# Sheet1.net
KiCad netlist of a schematic drawn in Altium Designer
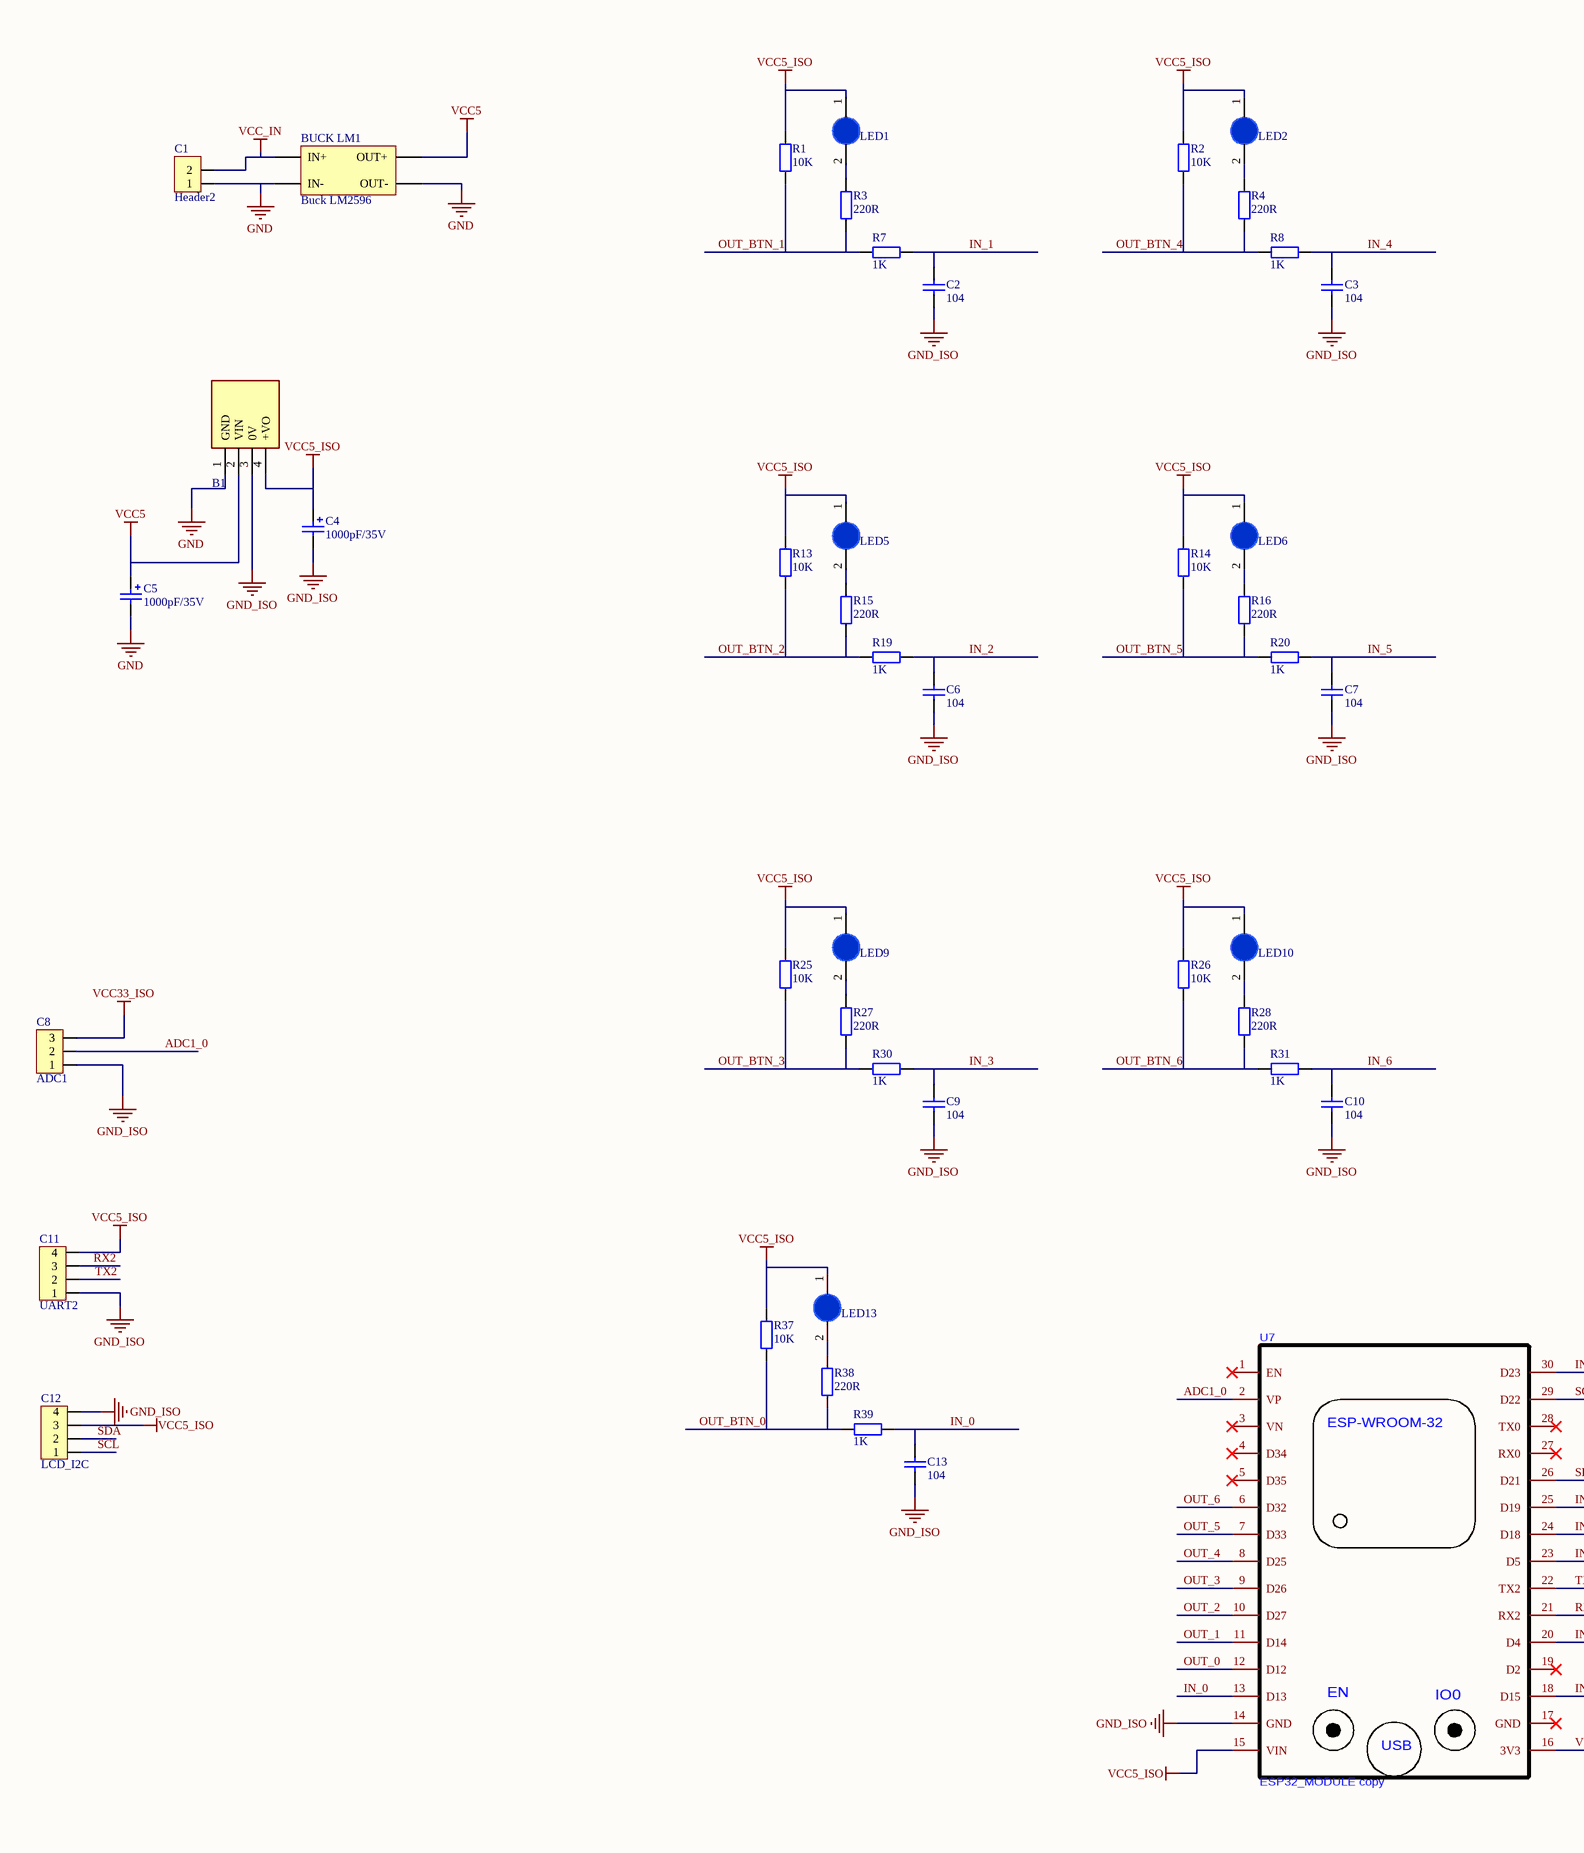
[diagram p0: Sheet1.SchDoc, left]
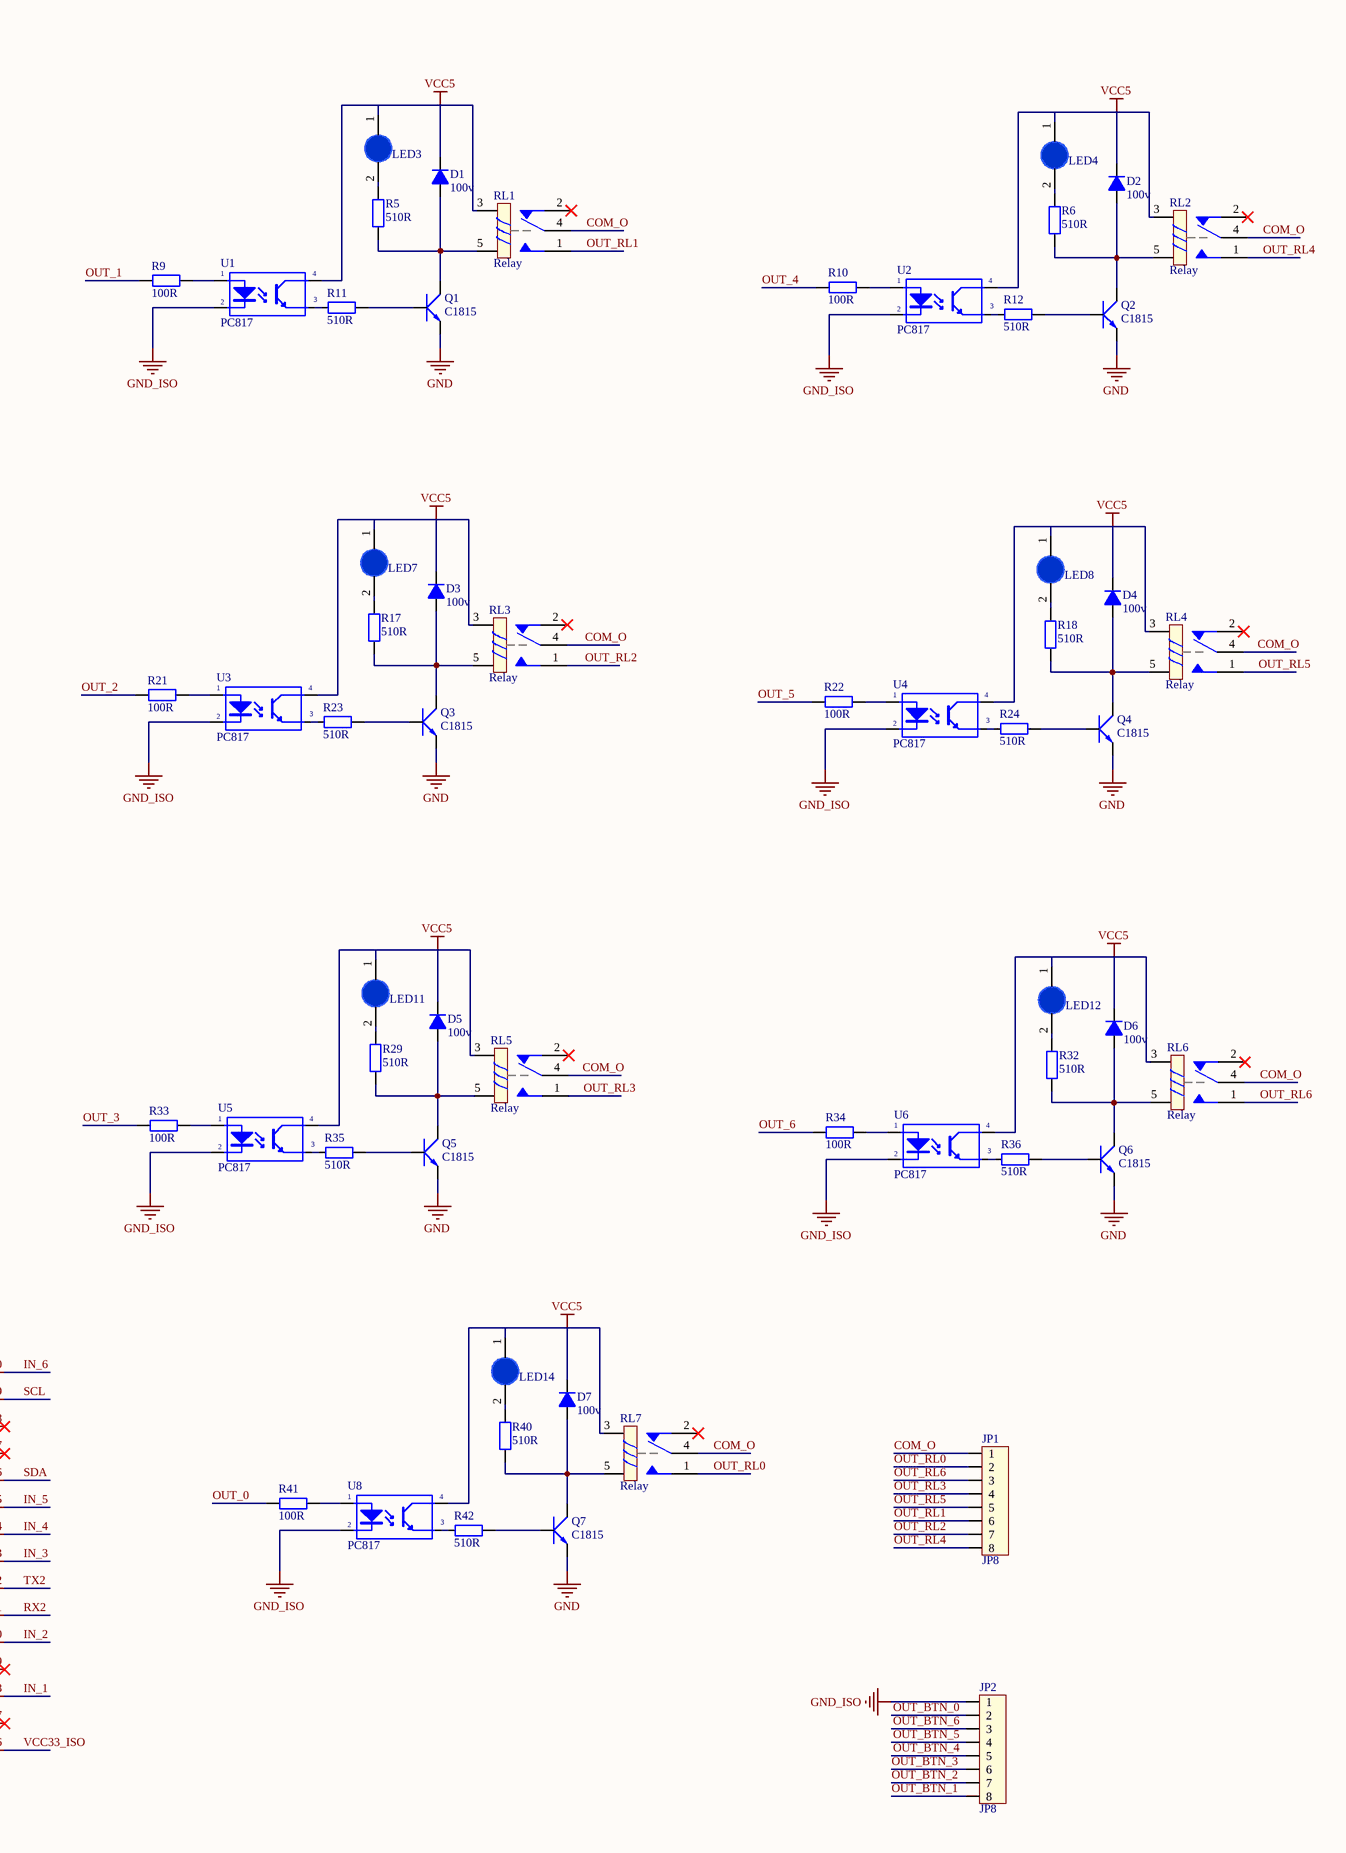
[diagram p1: Sheet1.SchDoc, right]

(export (version "E")
  (design (tool "Eeschema 10.0.6"))
  (components
    (comp (ref "B1")
      (value "B0505S1W")
      (footprint "B0505S1W")
      (description "Power Supply")
      (fields (field (name "MANUFACTURER_PART_NUMBER") "B0505S-1W"))
      (libsource (lib "myLib_v1") (part "B0505S1W"))
    )
    (comp (ref "BUCK LM1")
      (value "Buck LM2596")
      (footprint "BUCK LM2596")
      (libsource (lib "myLib_v1") (part "Buck LM2596"))
    )
    (comp (ref "C1")
      (value "Header2")
      (footprint "Header2")
      (description "Header IDC, 2 x 1 Pin Vertical 2.54mm Pitch (Non-Boxed, Male)")
      (fields
        (field (name "MANUFACTURER") "Würth Elektronik eiSos GmbH")
        (field (name "PARTNO") "613002143121")
        (field (name "CREATED BY") "Karrer Zheng")
      )
      (libsource (lib "myLib_v1") (part "Header2"))
    )
    (comp (ref "C2")
      (value "104")
      (footprint "tu gom")
      (description "Cắm")
      (libsource (lib "Altium_Lib_by_KhueNguyenCreator") (part "Tu gom 104 50V"))
    )
    (comp (ref "C3")
      (value "104")
      (footprint "tu gom")
      (description "Cắm")
      (libsource (lib "Altium_Lib_by_KhueNguyenCreator") (part "Tu gom 104 50V"))
    )
    (comp (ref "C4")
      (value "1000pF/35V")
      (footprint "CP2/5")
      (description "Polarized Capacitor (Surface Mount)")
      (fields (field (name "Comment") "Cap Pol3") (field (name "PUBLISHER") "Altium Limited"))
      (libsource (lib "myLib_v1") (part "Cap Pol3"))
    )
    (comp (ref "C5")
      (value "1000pF/35V")
      (footprint "CP2/5")
      (description "Polarized Capacitor (Surface Mount)")
      (fields (field (name "Comment") "Cap Pol3") (field (name "PUBLISHER") "Altium Limited"))
      (libsource (lib "myLib_v1") (part "Cap Pol3"))
    )
    (comp (ref "C6")
      (value "104")
      (footprint "tu gom")
      (description "Cắm")
      (libsource (lib "Altium_Lib_by_KhueNguyenCreator") (part "Tu gom 104 50V"))
    )
    (comp (ref "C7")
      (value "104")
      (footprint "tu gom")
      (description "Cắm")
      (libsource (lib "Altium_Lib_by_KhueNguyenCreator") (part "Tu gom 104 50V"))
    )
    (comp (ref "C8")
      (value "ADC1")
      (footprint "Header3")
      (description "Header IDC, 3 x 1 Pin Vertical 2.54mm Pitch (Non-Boxed, Male)")
      (fields
        (field (name "MANUFACTURER") "Würth Elektronik eiSos GmbH")
        (field (name "PARTNO") "613002143121")
        (field (name "CREATED BY") "Karrer Zheng")
      )
      (libsource (lib "myLib_v1") (part "Header3"))
    )
    (comp (ref "C9")
      (value "104")
      (footprint "tu gom")
      (description "Cắm")
      (libsource (lib "Altium_Lib_by_KhueNguyenCreator") (part "Tu gom 104 50V"))
    )
    (comp (ref "C10")
      (value "104")
      (footprint "tu gom")
      (description "Cắm")
      (libsource (lib "Altium_Lib_by_KhueNguyenCreator") (part "Tu gom 104 50V"))
    )
    (comp (ref "C11")
      (value "UART2")
      (footprint "Header4")
      (description "Header IDC, 4 x 1 Pin Vertical 2.54mm Pitch (Non-Boxed, Male)")
      (fields
        (field (name "MANUFACTURER") "Würth Elektronik eiSos GmbH")
        (field (name "PARTNO") "613002143121")
        (field (name "CREATED BY") "Karrer Zheng")
      )
      (libsource (lib "myLib_v1") (part "Header4"))
    )
    (comp (ref "C12")
      (value "LCD_I2C")
      (footprint "Header4")
      (description "Header IDC, 4 x 1 Pin Vertical 2.54mm Pitch (Non-Boxed, Male)")
      (fields
        (field (name "MANUFACTURER") "Würth Elektronik eiSos GmbH")
        (field (name "PARTNO") "613002143121")
        (field (name "CREATED BY") "Karrer Zheng")
      )
      (libsource (lib "myLib_v1") (part "Header4"))
    )
    (comp (ref "C13")
      (value "104")
      (footprint "tu gom")
      (description "Cắm")
      (libsource (lib "Altium_Lib_by_KhueNguyenCreator") (part "Tu gom 104 50V"))
    )
    (comp (ref "D1")
      (value "100v")
      (footprint "DIODE 0.5A")
      (description "Cắm")
      (libsource (lib "Altium_Lib_by_KhueNguyenCreator") (part "Diode 1N4148"))
    )
    (comp (ref "D2")
      (value "100v")
      (footprint "DIODE 0.5A")
      (description "Cắm")
      (libsource (lib "Altium_Lib_by_KhueNguyenCreator") (part "Diode 1N4148"))
    )
    (comp (ref "D3")
      (value "100v")
      (footprint "DIODE 0.5A")
      (description "Cắm")
      (libsource (lib "Altium_Lib_by_KhueNguyenCreator") (part "Diode 1N4148"))
    )
    (comp (ref "D4")
      (value "100v")
      (footprint "DIODE 0.5A")
      (description "Cắm")
      (libsource (lib "Altium_Lib_by_KhueNguyenCreator") (part "Diode 1N4148"))
    )
    (comp (ref "D5")
      (value "100v")
      (footprint "DIODE 0.5A")
      (description "Cắm")
      (libsource (lib "Altium_Lib_by_KhueNguyenCreator") (part "Diode 1N4148"))
    )
    (comp (ref "D6")
      (value "100v")
      (footprint "DIODE 0.5A")
      (description "Cắm")
      (libsource (lib "Altium_Lib_by_KhueNguyenCreator") (part "Diode 1N4148"))
    )
    (comp (ref "D7")
      (value "100v")
      (footprint "DIODE 0.5A")
      (description "Cắm")
      (libsource (lib "Altium_Lib_by_KhueNguyenCreator") (part "Diode 1N4148"))
    )
    (comp (ref "JP1")
      (value "JP8")
      (footprint "Header8")
      (description "Connector 8")
      (libsource (lib "myLib_v1") (part "Header8"))
    )
    (comp (ref "JP2")
      (value "JP8")
      (footprint "Header8")
      (description "Connector 8")
      (libsource (lib "myLib_v1") (part "Header8"))
    )
    (comp (ref "LED1")
      (value "LED 3mm")
      (footprint "LED-3MM-BLUE")
      (description "Cắm")
      (libsource (lib "myLib_v1") (part "LED 3mm Xanh Duong"))
    )
    (comp (ref "LED2")
      (value "LED 3mm")
      (footprint "LED-3MM-BLUE")
      (description "Cắm")
      (libsource (lib "myLib_v1") (part "LED 3mm Xanh Duong"))
    )
    (comp (ref "LED3")
      (value "LED 3mm")
      (footprint "LED-3MM-BLUE")
      (description "Cắm")
      (libsource (lib "myLib_v1") (part "LED 3mm Xanh Duong"))
    )
    (comp (ref "LED4")
      (value "LED 3mm")
      (footprint "LED-3MM-BLUE")
      (description "Cắm")
      (libsource (lib "myLib_v1") (part "LED 3mm Xanh Duong"))
    )
    (comp (ref "LED5")
      (value "LED 3mm")
      (footprint "LED-3MM-BLUE")
      (description "Cắm")
      (libsource (lib "myLib_v1") (part "LED 3mm Xanh Duong"))
    )
    (comp (ref "LED6")
      (value "LED 3mm")
      (footprint "LED-3MM-BLUE")
      (description "Cắm")
      (libsource (lib "myLib_v1") (part "LED 3mm Xanh Duong"))
    )
    (comp (ref "LED7")
      (value "LED 3mm")
      (footprint "LED-3MM-BLUE")
      (description "Cắm")
      (libsource (lib "myLib_v1") (part "LED 3mm Xanh Duong"))
    )
    (comp (ref "LED8")
      (value "LED 3mm")
      (footprint "LED-3MM-BLUE")
      (description "Cắm")
      (libsource (lib "myLib_v1") (part "LED 3mm Xanh Duong"))
    )
    (comp (ref "LED9")
      (value "LED 3mm")
      (footprint "LED-3MM-BLUE")
      (description "Cắm")
      (libsource (lib "myLib_v1") (part "LED 3mm Xanh Duong"))
    )
    (comp (ref "LED10")
      (value "LED 3mm")
      (footprint "LED-3MM-BLUE")
      (description "Cắm")
      (libsource (lib "myLib_v1") (part "LED 3mm Xanh Duong"))
    )
    (comp (ref "LED11")
      (value "LED 3mm")
      (footprint "LED-3MM-BLUE")
      (description "Cắm")
      (libsource (lib "myLib_v1") (part "LED 3mm Xanh Duong"))
    )
    (comp (ref "LED12")
      (value "LED 3mm")
      (footprint "LED-3MM-BLUE")
      (description "Cắm")
      (libsource (lib "myLib_v1") (part "LED 3mm Xanh Duong"))
    )
    (comp (ref "LED13")
      (value "LED 3mm")
      (footprint "LED-3MM-BLUE")
      (description "Cắm")
      (libsource (lib "myLib_v1") (part "LED 3mm Xanh Duong"))
    )
    (comp (ref "LED14")
      (value "LED 3mm")
      (footprint "LED-3MM-BLUE")
      (description "Cắm")
      (libsource (lib "myLib_v1") (part "LED 3mm Xanh Duong"))
    )
    (comp (ref "Q1")
      (value "C1815")
      (footprint "C1815_cam")
      (description "NPN 600mW, ECB")
      (libsource (lib "myLib_v1") (part "C1815"))
    )
    (comp (ref "Q2")
      (value "C1815")
      (footprint "C1815_cam")
      (description "NPN 600mW, ECB")
      (libsource (lib "myLib_v1") (part "C1815"))
    )
    (comp (ref "Q3")
      (value "C1815")
      (footprint "C1815_cam")
      (description "NPN 600mW, ECB")
      (libsource (lib "myLib_v1") (part "C1815"))
    )
    (comp (ref "Q4")
      (value "C1815")
      (footprint "C1815_cam")
      (description "NPN 600mW, ECB")
      (libsource (lib "myLib_v1") (part "C1815"))
    )
    (comp (ref "Q5")
      (value "C1815")
      (footprint "C1815_cam")
      (description "NPN 600mW, ECB")
      (libsource (lib "myLib_v1") (part "C1815"))
    )
    (comp (ref "Q6")
      (value "C1815")
      (footprint "C1815_cam")
      (description "NPN 600mW, ECB")
      (libsource (lib "myLib_v1") (part "C1815"))
    )
    (comp (ref "Q7")
      (value "C1815")
      (footprint "C1815_cam")
      (description "NPN 600mW, ECB")
      (libsource (lib "myLib_v1") (part "C1815"))
    )
    (comp (ref "R1")
      (value "10K")
      (footprint "R1/4W")
      (description "Resistor 1/4W")
      (libsource (lib "myLib_v1") (part "R1/4W"))
    )
    (comp (ref "R2")
      (value "10K")
      (footprint "R1/4W")
      (description "Resistor 1/4W")
      (libsource (lib "myLib_v1") (part "R1/4W"))
    )
    (comp (ref "R3")
      (value "220R")
      (footprint "R1/4W")
      (description "Resistor 1/4W")
      (libsource (lib "myLib_v1") (part "R1/4W"))
    )
    (comp (ref "R4")
      (value "220R")
      (footprint "R1/4W")
      (description "Resistor 1/4W")
      (libsource (lib "myLib_v1") (part "R1/4W"))
    )
    (comp (ref "R5")
      (value "510R")
      (footprint "R1/4W")
      (description "Resistor 1/4W")
      (libsource (lib "myLib_v1") (part "R1/4W"))
    )
    (comp (ref "R6")
      (value "510R")
      (footprint "R1/4W")
      (description "Resistor 1/4W")
      (libsource (lib "myLib_v1") (part "R1/4W"))
    )
    (comp (ref "R7")
      (value "1K")
      (footprint "R1/4W")
      (description "Resistor 1/4W")
      (libsource (lib "myLib_v1") (part "R1/4W"))
    )
    (comp (ref "R8")
      (value "1K")
      (footprint "R1/4W")
      (description "Resistor 1/4W")
      (libsource (lib "myLib_v1") (part "R1/4W"))
    )
    (comp (ref "R9")
      (value "100R")
      (footprint "R1/4W")
      (description "Resistor 1/4W")
      (libsource (lib "myLib_v1") (part "R1/4W"))
    )
    (comp (ref "R10")
      (value "100R")
      (footprint "R1/4W")
      (description "Resistor 1/4W")
      (libsource (lib "myLib_v1") (part "R1/4W"))
    )
    (comp (ref "R11")
      (value "510R")
      (footprint "R1/4W")
      (description "Resistor 1/4W")
      (libsource (lib "myLib_v1") (part "R1/4W"))
    )
    (comp (ref "R12")
      (value "510R")
      (footprint "R1/4W")
      (description "Resistor 1/4W")
      (libsource (lib "myLib_v1") (part "R1/4W"))
    )
    (comp (ref "R13")
      (value "10K")
      (footprint "R1/4W")
      (description "Resistor 1/4W")
      (libsource (lib "myLib_v1") (part "R1/4W"))
    )
    (comp (ref "R14")
      (value "10K")
      (footprint "R1/4W")
      (description "Resistor 1/4W")
      (libsource (lib "myLib_v1") (part "R1/4W"))
    )
    (comp (ref "R15")
      (value "220R")
      (footprint "R1/4W")
      (description "Resistor 1/4W")
      (libsource (lib "myLib_v1") (part "R1/4W"))
    )
    (comp (ref "R16")
      (value "220R")
      (footprint "R1/4W")
      (description "Resistor 1/4W")
      (libsource (lib "myLib_v1") (part "R1/4W"))
    )
    (comp (ref "R17")
      (value "510R")
      (footprint "R1/4W")
      (description "Resistor 1/4W")
      (libsource (lib "myLib_v1") (part "R1/4W"))
    )
    (comp (ref "R18")
      (value "510R")
      (footprint "R1/4W")
      (description "Resistor 1/4W")
      (libsource (lib "myLib_v1") (part "R1/4W"))
    )
    (comp (ref "R19")
      (value "1K")
      (footprint "R1/4W")
      (description "Resistor 1/4W")
      (libsource (lib "myLib_v1") (part "R1/4W"))
    )
    (comp (ref "R20")
      (value "1K")
      (footprint "R1/4W")
      (description "Resistor 1/4W")
      (libsource (lib "myLib_v1") (part "R1/4W"))
    )
    (comp (ref "R21")
      (value "100R")
      (footprint "R1/4W")
      (description "Resistor 1/4W")
      (libsource (lib "myLib_v1") (part "R1/4W"))
    )
    (comp (ref "R22")
      (value "100R")
      (footprint "R1/4W")
      (description "Resistor 1/4W")
      (libsource (lib "myLib_v1") (part "R1/4W"))
    )
    (comp (ref "R23")
      (value "510R")
      (footprint "R1/4W")
      (description "Resistor 1/4W")
      (libsource (lib "myLib_v1") (part "R1/4W"))
    )
    (comp (ref "R24")
      (value "510R")
      (footprint "R1/4W")
      (description "Resistor 1/4W")
      (libsource (lib "myLib_v1") (part "R1/4W"))
    )
    (comp (ref "R25")
      (value "10K")
      (footprint "R1/4W")
      (description "Resistor 1/4W")
      (libsource (lib "myLib_v1") (part "R1/4W"))
    )
    (comp (ref "R26")
      (value "10K")
      (footprint "R1/4W")
      (description "Resistor 1/4W")
      (libsource (lib "myLib_v1") (part "R1/4W"))
    )
    (comp (ref "R27")
      (value "220R")
      (footprint "R1/4W")
      (description "Resistor 1/4W")
      (libsource (lib "myLib_v1") (part "R1/4W"))
    )
    (comp (ref "R28")
      (value "220R")
      (footprint "R1/4W")
      (description "Resistor 1/4W")
      (libsource (lib "myLib_v1") (part "R1/4W"))
    )
    (comp (ref "R29")
      (value "510R")
      (footprint "R1/4W")
      (description "Resistor 1/4W")
      (libsource (lib "myLib_v1") (part "R1/4W"))
    )
    (comp (ref "R30")
      (value "1K")
      (footprint "R1/4W")
      (description "Resistor 1/4W")
      (libsource (lib "myLib_v1") (part "R1/4W"))
    )
    (comp (ref "R31")
      (value "1K")
      (footprint "R1/4W")
      (description "Resistor 1/4W")
      (libsource (lib "myLib_v1") (part "R1/4W"))
    )
    (comp (ref "R32")
      (value "510R")
      (footprint "R1/4W")
      (description "Resistor 1/4W")
      (libsource (lib "myLib_v1") (part "R1/4W"))
    )
    (comp (ref "R33")
      (value "100R")
      (footprint "R1/4W")
      (description "Resistor 1/4W")
      (libsource (lib "myLib_v1") (part "R1/4W"))
    )
    (comp (ref "R34")
      (value "100R")
      (footprint "R1/4W")
      (description "Resistor 1/4W")
      (libsource (lib "myLib_v1") (part "R1/4W"))
    )
    (comp (ref "R35")
      (value "510R")
      (footprint "R1/4W")
      (description "Resistor 1/4W")
      (libsource (lib "myLib_v1") (part "R1/4W"))
    )
    (comp (ref "R36")
      (value "510R")
      (footprint "R1/4W")
      (description "Resistor 1/4W")
      (libsource (lib "myLib_v1") (part "R1/4W"))
    )
    (comp (ref "R37")
      (value "10K")
      (footprint "R1/4W")
      (description "Resistor 1/4W")
      (libsource (lib "myLib_v1") (part "R1/4W"))
    )
    (comp (ref "R38")
      (value "220R")
      (footprint "R1/4W")
      (description "Resistor 1/4W")
      (libsource (lib "myLib_v1") (part "R1/4W"))
    )
    (comp (ref "R39")
      (value "1K")
      (footprint "R1/4W")
      (description "Resistor 1/4W")
      (libsource (lib "myLib_v1") (part "R1/4W"))
    )
    (comp (ref "R40")
      (value "510R")
      (footprint "R1/4W")
      (description "Resistor 1/4W")
      (libsource (lib "myLib_v1") (part "R1/4W"))
    )
    (comp (ref "R41")
      (value "100R")
      (footprint "R1/4W")
      (description "Resistor 1/4W")
      (libsource (lib "myLib_v1") (part "R1/4W"))
    )
    (comp (ref "R42")
      (value "510R")
      (footprint "R1/4W")
      (description "Resistor 1/4W")
      (libsource (lib "myLib_v1") (part "R1/4W"))
    )
    (comp (ref "RL1")
      (value "Relay")
      (footprint "RELAY_SRA_05VDC_SL_C")
      (description "Relay 5 Chan")
      (libsource (lib "myLib_v1") (part "RL_SRA-05VDC-SL-C"))
    )
    (comp (ref "RL2")
      (value "Relay")
      (footprint "RELAY_SRA_05VDC_SL_C")
      (description "Relay 5 Chan")
      (libsource (lib "myLib_v1") (part "RL_SRA-05VDC-SL-C"))
    )
    (comp (ref "RL3")
      (value "Relay")
      (footprint "RELAY_SRA_05VDC_SL_C")
      (description "Relay 5 Chan")
      (libsource (lib "myLib_v1") (part "RL_SRA-05VDC-SL-C"))
    )
    (comp (ref "RL4")
      (value "Relay")
      (footprint "RELAY_SRA_05VDC_SL_C")
      (description "Relay 5 Chan")
      (libsource (lib "myLib_v1") (part "RL_SRA-05VDC-SL-C"))
    )
    (comp (ref "RL5")
      (value "Relay")
      (footprint "RELAY_SRA_05VDC_SL_C")
      (description "Relay 5 Chan")
      (libsource (lib "myLib_v1") (part "RL_SRA-05VDC-SL-C"))
    )
    (comp (ref "RL6")
      (value "Relay")
      (footprint "RELAY_SRA_05VDC_SL_C")
      (description "Relay 5 Chan")
      (libsource (lib "myLib_v1") (part "RL_SRA-05VDC-SL-C"))
    )
    (comp (ref "RL7")
      (value "Relay")
      (footprint "RELAY_SRA_05VDC_SL_C")
      (description "Relay 5 Chan")
      (libsource (lib "myLib_v1") (part "RL_SRA-05VDC-SL-C"))
    )
    (comp (ref "U1")
      (value "PC817")
      (footprint "DIP4/W0.3")
      (description "Single Opto")
      (libsource (lib "myLib_v1") (part "PC817"))
    )
    (comp (ref "U2")
      (value "PC817")
      (footprint "DIP4/W0.3")
      (description "Single Opto")
      (libsource (lib "myLib_v1") (part "PC817"))
    )
    (comp (ref "U3")
      (value "PC817")
      (footprint "DIP4/W0.3")
      (description "Single Opto")
      (libsource (lib "myLib_v1") (part "PC817"))
    )
    (comp (ref "U4")
      (value "PC817")
      (footprint "DIP4/W0.3")
      (description "Single Opto")
      (libsource (lib "myLib_v1") (part "PC817"))
    )
    (comp (ref "U5")
      (value "PC817")
      (footprint "DIP4/W0.3")
      (description "Single Opto")
      (libsource (lib "myLib_v1") (part "PC817"))
    )
    (comp (ref "U6")
      (value "PC817")
      (footprint "DIP4/W0.3")
      (description "Single Opto")
      (libsource (lib "myLib_v1") (part "PC817"))
    )
    (comp (ref "U7")
      (value "ESP32_MODULE copy")
      (footprint "ESP32-WIFIMODULE-FOOTPRINT")
      (libsource (lib "myLib_v1") (part "ESP32_MODULE copy"))
    )
    (comp (ref "U8")
      (value "PC817")
      (footprint "DIP4/W0.3")
      (description "Single Opto")
      (libsource (lib "myLib_v1") (part "PC817"))
    )
  )
  (nets
    (net (code "1") (name "/ADC1_0") (class "Default")
      (node (ref "C8") (pin "2") (pinfunction "2_2") (pintype "passive"))
      (node (ref "U7") (pin "2") (pinfunction "VP_2") (pintype "passive"))
    )
    (net (code "2") (name "/COM_O") (class "Default")
      (node (ref "JP1") (pin "1") (pinfunction "1_1") (pintype "passive"))
      (node (ref "RL1") (pin "4") (pinfunction "4_4") (pintype "passive"))
      (node (ref "RL2") (pin "4") (pinfunction "4_4") (pintype "passive"))
      (node (ref "RL3") (pin "4") (pinfunction "4_4") (pintype "passive"))
      (node (ref "RL4") (pin "4") (pinfunction "4_4") (pintype "passive"))
      (node (ref "RL5") (pin "4") (pinfunction "4_4") (pintype "passive"))
      (node (ref "RL6") (pin "4") (pinfunction "4_4") (pintype "passive"))
      (node (ref "RL7") (pin "4") (pinfunction "4_4") (pintype "passive"))
    )
    (net (code "3") (name "/IN_0") (class "Default")
      (node (ref "C13") (pin "1") (pinfunction "1_1") (pintype "passive"))
      (node (ref "R39") (pin "1") (pinfunction "1_1") (pintype "passive"))
      (node (ref "U7") (pin "13") (pinfunction "D13_13") (pintype "passive"))
    )
    (net (code "4") (name "/IN_1") (class "Default")
      (node (ref "C2") (pin "1") (pinfunction "1_1") (pintype "passive"))
      (node (ref "R7") (pin "1") (pinfunction "1_1") (pintype "passive"))
      (node (ref "U7") (pin "18") (pinfunction "D15_18") (pintype "passive"))
    )
    (net (code "5") (name "/IN_2") (class "Default")
      (node (ref "C6") (pin "1") (pinfunction "1_1") (pintype "passive"))
      (node (ref "R19") (pin "1") (pinfunction "1_1") (pintype "passive"))
      (node (ref "U7") (pin "20") (pinfunction "D4_20") (pintype "passive"))
    )
    (net (code "6") (name "/IN_3") (class "Default")
      (node (ref "C9") (pin "1") (pinfunction "1_1") (pintype "passive"))
      (node (ref "R30") (pin "1") (pinfunction "1_1") (pintype "passive"))
      (node (ref "U7") (pin "23") (pinfunction "D5_23") (pintype "passive"))
    )
    (net (code "7") (name "/IN_4") (class "Default")
      (node (ref "C3") (pin "1") (pinfunction "1_1") (pintype "passive"))
      (node (ref "R8") (pin "1") (pinfunction "1_1") (pintype "passive"))
      (node (ref "U7") (pin "24") (pinfunction "D18_24") (pintype "passive"))
    )
    (net (code "8") (name "/IN_5") (class "Default")
      (node (ref "C7") (pin "1") (pinfunction "1_1") (pintype "passive"))
      (node (ref "R20") (pin "1") (pinfunction "1_1") (pintype "passive"))
      (node (ref "U7") (pin "25") (pinfunction "D19_25") (pintype "passive"))
    )
    (net (code "9") (name "/IN_6") (class "Default")
      (node (ref "C10") (pin "1") (pinfunction "1_1") (pintype "passive"))
      (node (ref "R31") (pin "1") (pinfunction "1_1") (pintype "passive"))
      (node (ref "U7") (pin "30") (pinfunction "D23_30") (pintype "passive"))
    )
    (net (code "10") (name "/OUT_0") (class "Default")
      (node (ref "R41") (pin "1") (pinfunction "1_1") (pintype "passive"))
      (node (ref "U7") (pin "12") (pinfunction "D12_12") (pintype "passive"))
    )
    (net (code "11") (name "/OUT_1") (class "Default")
      (node (ref "R9") (pin "1") (pinfunction "1_1") (pintype "passive"))
      (node (ref "U7") (pin "11") (pinfunction "D14_11") (pintype "passive"))
    )
    (net (code "12") (name "/OUT_2") (class "Default")
      (node (ref "R21") (pin "1") (pinfunction "1_1") (pintype "passive"))
      (node (ref "U7") (pin "10") (pinfunction "D27_10") (pintype "passive"))
    )
    (net (code "13") (name "/OUT_3") (class "Default")
      (node (ref "R33") (pin "1") (pinfunction "1_1") (pintype "passive"))
      (node (ref "U7") (pin "9") (pinfunction "D26_9") (pintype "passive"))
    )
    (net (code "14") (name "/OUT_4") (class "Default")
      (node (ref "R10") (pin "1") (pinfunction "1_1") (pintype "passive"))
      (node (ref "U7") (pin "8") (pinfunction "D25_8") (pintype "passive"))
    )
    (net (code "15") (name "/OUT_5") (class "Default")
      (node (ref "R22") (pin "1") (pinfunction "1_1") (pintype "passive"))
      (node (ref "U7") (pin "7") (pinfunction "D33_7") (pintype "passive"))
    )
    (net (code "16") (name "/OUT_6") (class "Default")
      (node (ref "R34") (pin "1") (pinfunction "1_1") (pintype "passive"))
      (node (ref "U7") (pin "6") (pinfunction "D32_6") (pintype "passive"))
    )
    (net (code "17") (name "/OUT_BTN_0") (class "Default")
      (node (ref "JP2") (pin "2") (pinfunction "2_2") (pintype "passive"))
      (node (ref "R37") (pin "1") (pinfunction "1_1") (pintype "passive"))
      (node (ref "R38") (pin "1") (pinfunction "1_1") (pintype "passive"))
      (node (ref "R39") (pin "2") (pinfunction "2_2") (pintype "passive"))
    )
    (net (code "18") (name "/OUT_BTN_1") (class "Default")
      (node (ref "JP2") (pin "8") (pinfunction "8_8") (pintype "passive"))
      (node (ref "R1") (pin "1") (pinfunction "1_1") (pintype "passive"))
      (node (ref "R3") (pin "1") (pinfunction "1_1") (pintype "passive"))
      (node (ref "R7") (pin "2") (pinfunction "2_2") (pintype "passive"))
    )
    (net (code "19") (name "/OUT_BTN_2") (class "Default")
      (node (ref "JP2") (pin "7") (pinfunction "7_7") (pintype "passive"))
      (node (ref "R13") (pin "1") (pinfunction "1_1") (pintype "passive"))
      (node (ref "R15") (pin "1") (pinfunction "1_1") (pintype "passive"))
      (node (ref "R19") (pin "2") (pinfunction "2_2") (pintype "passive"))
    )
    (net (code "20") (name "/OUT_BTN_3") (class "Default")
      (node (ref "JP2") (pin "6") (pinfunction "6_6") (pintype "passive"))
      (node (ref "R25") (pin "1") (pinfunction "1_1") (pintype "passive"))
      (node (ref "R27") (pin "1") (pinfunction "1_1") (pintype "passive"))
      (node (ref "R30") (pin "2") (pinfunction "2_2") (pintype "passive"))
    )
    (net (code "21") (name "/OUT_BTN_4") (class "Default")
      (node (ref "JP2") (pin "5") (pinfunction "5_5") (pintype "passive"))
      (node (ref "R2") (pin "1") (pinfunction "1_1") (pintype "passive"))
      (node (ref "R4") (pin "1") (pinfunction "1_1") (pintype "passive"))
      (node (ref "R8") (pin "2") (pinfunction "2_2") (pintype "passive"))
    )
    (net (code "22") (name "/OUT_BTN_5") (class "Default")
      (node (ref "JP2") (pin "4") (pinfunction "4_4") (pintype "passive"))
      (node (ref "R14") (pin "1") (pinfunction "1_1") (pintype "passive"))
      (node (ref "R16") (pin "1") (pinfunction "1_1") (pintype "passive"))
      (node (ref "R20") (pin "2") (pinfunction "2_2") (pintype "passive"))
    )
    (net (code "23") (name "/OUT_BTN_6") (class "Default")
      (node (ref "JP2") (pin "3") (pinfunction "3_3") (pintype "passive"))
      (node (ref "R26") (pin "1") (pinfunction "1_1") (pintype "passive"))
      (node (ref "R28") (pin "1") (pinfunction "1_1") (pintype "passive"))
      (node (ref "R31") (pin "2") (pinfunction "2_2") (pintype "passive"))
    )
    (net (code "24") (name "/OUT_RL0") (class "Default")
      (node (ref "JP1") (pin "2") (pinfunction "2_2") (pintype "passive"))
      (node (ref "RL7") (pin "1") (pinfunction "1_1") (pintype "passive"))
    )
    (net (code "25") (name "/OUT_RL1") (class "Default")
      (node (ref "JP1") (pin "6") (pinfunction "6_6") (pintype "passive"))
      (node (ref "RL1") (pin "1") (pinfunction "1_1") (pintype "passive"))
    )
    (net (code "26") (name "/OUT_RL2") (class "Default")
      (node (ref "JP1") (pin "7") (pinfunction "7_7") (pintype "passive"))
      (node (ref "RL3") (pin "1") (pinfunction "1_1") (pintype "passive"))
    )
    (net (code "27") (name "/OUT_RL3") (class "Default")
      (node (ref "JP1") (pin "4") (pinfunction "4_4") (pintype "passive"))
      (node (ref "RL5") (pin "1") (pinfunction "1_1") (pintype "passive"))
    )
    (net (code "28") (name "/OUT_RL4") (class "Default")
      (node (ref "JP1") (pin "8") (pinfunction "8_8") (pintype "passive"))
      (node (ref "RL2") (pin "1") (pinfunction "1_1") (pintype "passive"))
    )
    (net (code "29") (name "/OUT_RL5") (class "Default")
      (node (ref "JP1") (pin "5") (pinfunction "5_5") (pintype "passive"))
      (node (ref "RL4") (pin "1") (pinfunction "1_1") (pintype "passive"))
    )
    (net (code "30") (name "/OUT_RL6") (class "Default")
      (node (ref "JP1") (pin "3") (pinfunction "3_3") (pintype "passive"))
      (node (ref "RL6") (pin "1") (pinfunction "1_1") (pintype "passive"))
    )
    (net (code "31") (name "/RX2") (class "Default")
      (node (ref "C11") (pin "3") (pinfunction "3_3") (pintype "passive"))
      (node (ref "U7") (pin "21") (pinfunction "RX2_21") (pintype "passive"))
    )
    (net (code "32") (name "/SCL") (class "Default")
      (node (ref "C12") (pin "1") (pinfunction "1_1") (pintype "passive"))
      (node (ref "U7") (pin "29") (pinfunction "D22_29") (pintype "passive"))
    )
    (net (code "33") (name "/SDA") (class "Default")
      (node (ref "C12") (pin "2") (pinfunction "2_2") (pintype "passive"))
      (node (ref "U7") (pin "26") (pinfunction "D21_26") (pintype "passive"))
    )
    (net (code "34") (name "/TX2") (class "Default")
      (node (ref "C11") (pin "2") (pinfunction "2_2") (pintype "passive"))
      (node (ref "U7") (pin "22") (pinfunction "TX2_22") (pintype "passive"))
    )
    (net (code "35") (name "GND") (class "Default")
      (node (ref "B1") (pin "1") (pinfunction "GND_1") (pintype "passive"))
      (node (ref "BUCK LM1") (pin "2") (pinfunction "IN-_2") (pintype "passive"))
      (node (ref "BUCK LM1") (pin "3") (pinfunction "OUT-_3") (pintype "passive"))
      (node (ref "C1") (pin "1") (pinfunction "1_1") (pintype "passive"))
      (node (ref "C5") (pin "2") (pinfunction "2_2") (pintype "passive"))
      (node (ref "Q1") (pin "1") (pinfunction "E_1") (pintype "passive"))
      (node (ref "Q2") (pin "1") (pinfunction "E_1") (pintype "passive"))
      (node (ref "Q3") (pin "1") (pinfunction "E_1") (pintype "passive"))
      (node (ref "Q4") (pin "1") (pinfunction "E_1") (pintype "passive"))
      (node (ref "Q5") (pin "1") (pinfunction "E_1") (pintype "passive"))
      (node (ref "Q6") (pin "1") (pinfunction "E_1") (pintype "passive"))
      (node (ref "Q7") (pin "1") (pinfunction "E_1") (pintype "passive"))
    )
    (net (code "36") (name "GND_ISO") (class "Default")
      (node (ref "B1") (pin "3") (pinfunction "0V_3") (pintype "passive"))
      (node (ref "C10") (pin "2") (pinfunction "2_2") (pintype "passive"))
      (node (ref "C11") (pin "1") (pinfunction "1_1") (pintype "passive"))
      (node (ref "C12") (pin "4") (pinfunction "4_4") (pintype "passive"))
      (node (ref "C13") (pin "2") (pinfunction "2_2") (pintype "passive"))
      (node (ref "C2") (pin "2") (pinfunction "2_2") (pintype "passive"))
      (node (ref "C3") (pin "2") (pinfunction "2_2") (pintype "passive"))
      (node (ref "C4") (pin "2") (pinfunction "2_2") (pintype "passive"))
      (node (ref "C6") (pin "2") (pinfunction "2_2") (pintype "passive"))
      (node (ref "C7") (pin "2") (pinfunction "2_2") (pintype "passive"))
      (node (ref "C8") (pin "1") (pinfunction "1_1") (pintype "passive"))
      (node (ref "C9") (pin "2") (pinfunction "2_2") (pintype "passive"))
      (node (ref "JP2") (pin "1") (pinfunction "1_1") (pintype "passive"))
      (node (ref "U1") (pin "2") (pinfunction "K_2") (pintype "passive"))
      (node (ref "U2") (pin "2") (pinfunction "K_2") (pintype "passive"))
      (node (ref "U3") (pin "2") (pinfunction "K_2") (pintype "passive"))
      (node (ref "U4") (pin "2") (pinfunction "K_2") (pintype "passive"))
      (node (ref "U5") (pin "2") (pinfunction "K_2") (pintype "passive"))
      (node (ref "U6") (pin "2") (pinfunction "K_2") (pintype "passive"))
      (node (ref "U7") (pin "14") (pinfunction "GND_14") (pintype "passive"))
      (node (ref "U8") (pin "2") (pinfunction "K_2") (pintype "passive"))
    )
    (net (code "37") (name "Net-(D1-A)") (class "Default")
      (node (ref "D1") (pin "1") (pinfunction "A_1") (pintype "passive"))
      (node (ref "Q1") (pin "2") (pinfunction "C_2") (pintype "passive"))
      (node (ref "R5") (pin "2") (pinfunction "2_2") (pintype "passive"))
      (node (ref "RL1") (pin "5") (pinfunction "5_5") (pintype "passive"))
    )
    (net (code "38") (name "Net-(D2-A)") (class "Default")
      (node (ref "D2") (pin "1") (pinfunction "A_1") (pintype "passive"))
      (node (ref "Q2") (pin "2") (pinfunction "C_2") (pintype "passive"))
      (node (ref "R6") (pin "2") (pinfunction "2_2") (pintype "passive"))
      (node (ref "RL2") (pin "5") (pinfunction "5_5") (pintype "passive"))
    )
    (net (code "39") (name "Net-(D3-A)") (class "Default")
      (node (ref "D3") (pin "1") (pinfunction "A_1") (pintype "passive"))
      (node (ref "Q3") (pin "2") (pinfunction "C_2") (pintype "passive"))
      (node (ref "R17") (pin "2") (pinfunction "2_2") (pintype "passive"))
      (node (ref "RL3") (pin "5") (pinfunction "5_5") (pintype "passive"))
    )
    (net (code "40") (name "Net-(D4-A)") (class "Default")
      (node (ref "D4") (pin "1") (pinfunction "A_1") (pintype "passive"))
      (node (ref "Q4") (pin "2") (pinfunction "C_2") (pintype "passive"))
      (node (ref "R18") (pin "2") (pinfunction "2_2") (pintype "passive"))
      (node (ref "RL4") (pin "5") (pinfunction "5_5") (pintype "passive"))
    )
    (net (code "41") (name "Net-(D5-A)") (class "Default")
      (node (ref "D5") (pin "1") (pinfunction "A_1") (pintype "passive"))
      (node (ref "Q5") (pin "2") (pinfunction "C_2") (pintype "passive"))
      (node (ref "R29") (pin "2") (pinfunction "2_2") (pintype "passive"))
      (node (ref "RL5") (pin "5") (pinfunction "5_5") (pintype "passive"))
    )
    (net (code "42") (name "Net-(D6-A)") (class "Default")
      (node (ref "D6") (pin "1") (pinfunction "A_1") (pintype "passive"))
      (node (ref "Q6") (pin "2") (pinfunction "C_2") (pintype "passive"))
      (node (ref "R32") (pin "2") (pinfunction "2_2") (pintype "passive"))
      (node (ref "RL6") (pin "5") (pinfunction "5_5") (pintype "passive"))
    )
    (net (code "43") (name "Net-(D7-A)") (class "Default")
      (node (ref "D7") (pin "1") (pinfunction "A_1") (pintype "passive"))
      (node (ref "Q7") (pin "2") (pinfunction "C_2") (pintype "passive"))
      (node (ref "R40") (pin "2") (pinfunction "2_2") (pintype "passive"))
      (node (ref "RL7") (pin "5") (pinfunction "5_5") (pintype "passive"))
    )
    (net (code "44") (name "Net-(LED1-K)") (class "Default")
      (node (ref "LED1") (pin "2") (pinfunction "K_2") (pintype "passive"))
      (node (ref "R3") (pin "2") (pinfunction "2_2") (pintype "passive"))
    )
    (net (code "45") (name "Net-(LED2-K)") (class "Default")
      (node (ref "LED2") (pin "2") (pinfunction "K_2") (pintype "passive"))
      (node (ref "R4") (pin "2") (pinfunction "2_2") (pintype "passive"))
    )
    (net (code "46") (name "Net-(LED3-K)") (class "Default")
      (node (ref "LED3") (pin "2") (pinfunction "K_2") (pintype "passive"))
      (node (ref "R5") (pin "1") (pinfunction "1_1") (pintype "passive"))
    )
    (net (code "47") (name "Net-(LED4-K)") (class "Default")
      (node (ref "LED4") (pin "2") (pinfunction "K_2") (pintype "passive"))
      (node (ref "R6") (pin "1") (pinfunction "1_1") (pintype "passive"))
    )
    (net (code "48") (name "Net-(LED5-K)") (class "Default")
      (node (ref "LED5") (pin "2") (pinfunction "K_2") (pintype "passive"))
      (node (ref "R15") (pin "2") (pinfunction "2_2") (pintype "passive"))
    )
    (net (code "49") (name "Net-(LED6-K)") (class "Default")
      (node (ref "LED6") (pin "2") (pinfunction "K_2") (pintype "passive"))
      (node (ref "R16") (pin "2") (pinfunction "2_2") (pintype "passive"))
    )
    (net (code "50") (name "Net-(LED7-K)") (class "Default")
      (node (ref "LED7") (pin "2") (pinfunction "K_2") (pintype "passive"))
      (node (ref "R17") (pin "1") (pinfunction "1_1") (pintype "passive"))
    )
    (net (code "51") (name "Net-(LED8-K)") (class "Default")
      (node (ref "LED8") (pin "2") (pinfunction "K_2") (pintype "passive"))
      (node (ref "R18") (pin "1") (pinfunction "1_1") (pintype "passive"))
    )
    (net (code "52") (name "Net-(LED9-K)") (class "Default")
      (node (ref "LED9") (pin "2") (pinfunction "K_2") (pintype "passive"))
      (node (ref "R27") (pin "2") (pinfunction "2_2") (pintype "passive"))
    )
    (net (code "53") (name "Net-(LED10-K)") (class "Default")
      (node (ref "LED10") (pin "2") (pinfunction "K_2") (pintype "passive"))
      (node (ref "R28") (pin "2") (pinfunction "2_2") (pintype "passive"))
    )
    (net (code "54") (name "Net-(LED11-K)") (class "Default")
      (node (ref "LED11") (pin "2") (pinfunction "K_2") (pintype "passive"))
      (node (ref "R29") (pin "1") (pinfunction "1_1") (pintype "passive"))
    )
    (net (code "55") (name "Net-(LED12-K)") (class "Default")
      (node (ref "LED12") (pin "2") (pinfunction "K_2") (pintype "passive"))
      (node (ref "R32") (pin "1") (pinfunction "1_1") (pintype "passive"))
    )
    (net (code "56") (name "Net-(LED13-K)") (class "Default")
      (node (ref "LED13") (pin "2") (pinfunction "K_2") (pintype "passive"))
      (node (ref "R38") (pin "2") (pinfunction "2_2") (pintype "passive"))
    )
    (net (code "57") (name "Net-(LED14-K)") (class "Default")
      (node (ref "LED14") (pin "2") (pinfunction "K_2") (pintype "passive"))
      (node (ref "R40") (pin "1") (pinfunction "1_1") (pintype "passive"))
    )
    (net (code "58") (name "Net-(Q1-B)") (class "Default")
      (node (ref "Q1") (pin "3") (pinfunction "B_3") (pintype "passive"))
      (node (ref "R11") (pin "2") (pinfunction "2_2") (pintype "passive"))
    )
    (net (code "59") (name "Net-(Q2-B)") (class "Default")
      (node (ref "Q2") (pin "3") (pinfunction "B_3") (pintype "passive"))
      (node (ref "R12") (pin "2") (pinfunction "2_2") (pintype "passive"))
    )
    (net (code "60") (name "Net-(Q3-B)") (class "Default")
      (node (ref "Q3") (pin "3") (pinfunction "B_3") (pintype "passive"))
      (node (ref "R23") (pin "2") (pinfunction "2_2") (pintype "passive"))
    )
    (net (code "61") (name "Net-(Q4-B)") (class "Default")
      (node (ref "Q4") (pin "3") (pinfunction "B_3") (pintype "passive"))
      (node (ref "R24") (pin "2") (pinfunction "2_2") (pintype "passive"))
    )
    (net (code "62") (name "Net-(Q5-B)") (class "Default")
      (node (ref "Q5") (pin "3") (pinfunction "B_3") (pintype "passive"))
      (node (ref "R35") (pin "2") (pinfunction "2_2") (pintype "passive"))
    )
    (net (code "63") (name "Net-(Q6-B)") (class "Default")
      (node (ref "Q6") (pin "3") (pinfunction "B_3") (pintype "passive"))
      (node (ref "R36") (pin "2") (pinfunction "2_2") (pintype "passive"))
    )
    (net (code "64") (name "Net-(Q7-B)") (class "Default")
      (node (ref "Q7") (pin "3") (pinfunction "B_3") (pintype "passive"))
      (node (ref "R42") (pin "2") (pinfunction "2_2") (pintype "passive"))
    )
    (net (code "65") (name "Net-(U1-A)") (class "Default")
      (node (ref "R9") (pin "2") (pinfunction "2_2") (pintype "passive"))
      (node (ref "U1") (pin "1") (pinfunction "A_1") (pintype "passive"))
    )
    (net (code "66") (name "Net-(U1-E)") (class "Default")
      (node (ref "R11") (pin "1") (pinfunction "1_1") (pintype "passive"))
      (node (ref "U1") (pin "3") (pinfunction "E_3") (pintype "passive"))
    )
    (net (code "67") (name "Net-(U2-A)") (class "Default")
      (node (ref "R10") (pin "2") (pinfunction "2_2") (pintype "passive"))
      (node (ref "U2") (pin "1") (pinfunction "A_1") (pintype "passive"))
    )
    (net (code "68") (name "Net-(U2-E)") (class "Default")
      (node (ref "R12") (pin "1") (pinfunction "1_1") (pintype "passive"))
      (node (ref "U2") (pin "3") (pinfunction "E_3") (pintype "passive"))
    )
    (net (code "69") (name "Net-(U3-A)") (class "Default")
      (node (ref "R21") (pin "2") (pinfunction "2_2") (pintype "passive"))
      (node (ref "U3") (pin "1") (pinfunction "A_1") (pintype "passive"))
    )
    (net (code "70") (name "Net-(U3-E)") (class "Default")
      (node (ref "R23") (pin "1") (pinfunction "1_1") (pintype "passive"))
      (node (ref "U3") (pin "3") (pinfunction "E_3") (pintype "passive"))
    )
    (net (code "71") (name "Net-(U4-A)") (class "Default")
      (node (ref "R22") (pin "2") (pinfunction "2_2") (pintype "passive"))
      (node (ref "U4") (pin "1") (pinfunction "A_1") (pintype "passive"))
    )
    (net (code "72") (name "Net-(U4-E)") (class "Default")
      (node (ref "R24") (pin "1") (pinfunction "1_1") (pintype "passive"))
      (node (ref "U4") (pin "3") (pinfunction "E_3") (pintype "passive"))
    )
    (net (code "73") (name "Net-(U5-A)") (class "Default")
      (node (ref "R33") (pin "2") (pinfunction "2_2") (pintype "passive"))
      (node (ref "U5") (pin "1") (pinfunction "A_1") (pintype "passive"))
    )
    (net (code "74") (name "Net-(U5-E)") (class "Default")
      (node (ref "R35") (pin "1") (pinfunction "1_1") (pintype "passive"))
      (node (ref "U5") (pin "3") (pinfunction "E_3") (pintype "passive"))
    )
    (net (code "75") (name "Net-(U6-A)") (class "Default")
      (node (ref "R34") (pin "2") (pinfunction "2_2") (pintype "passive"))
      (node (ref "U6") (pin "1") (pinfunction "A_1") (pintype "passive"))
    )
    (net (code "76") (name "Net-(U6-E)") (class "Default")
      (node (ref "R36") (pin "1") (pinfunction "1_1") (pintype "passive"))
      (node (ref "U6") (pin "3") (pinfunction "E_3") (pintype "passive"))
    )
    (net (code "77") (name "Net-(U8-A)") (class "Default")
      (node (ref "R41") (pin "2") (pinfunction "2_2") (pintype "passive"))
      (node (ref "U8") (pin "1") (pinfunction "A_1") (pintype "passive"))
    )
    (net (code "78") (name "Net-(U8-E)") (class "Default")
      (node (ref "R42") (pin "1") (pinfunction "1_1") (pintype "passive"))
      (node (ref "U8") (pin "3") (pinfunction "E_3") (pintype "passive"))
    )
    (net (code "79") (name "VCC5") (class "Default")
      (node (ref "B1") (pin "2") (pinfunction "VIN_2") (pintype "passive"))
      (node (ref "BUCK LM1") (pin "4") (pinfunction "OUT+_4") (pintype "passive"))
      (node (ref "C5") (pin "1") (pinfunction "1_1") (pintype "passive"))
      (node (ref "D1") (pin "2") (pinfunction "K_2") (pintype "passive"))
      (node (ref "D2") (pin "2") (pinfunction "K_2") (pintype "passive"))
      (node (ref "D3") (pin "2") (pinfunction "K_2") (pintype "passive"))
      (node (ref "D4") (pin "2") (pinfunction "K_2") (pintype "passive"))
      (node (ref "D5") (pin "2") (pinfunction "K_2") (pintype "passive"))
      (node (ref "D6") (pin "2") (pinfunction "K_2") (pintype "passive"))
      (node (ref "D7") (pin "2") (pinfunction "K_2") (pintype "passive"))
      (node (ref "LED11") (pin "1") (pinfunction "A_1") (pintype "passive"))
      (node (ref "LED12") (pin "1") (pinfunction "A_1") (pintype "passive"))
      (node (ref "LED14") (pin "1") (pinfunction "A_1") (pintype "passive"))
      (node (ref "LED3") (pin "1") (pinfunction "A_1") (pintype "passive"))
      (node (ref "LED4") (pin "1") (pinfunction "A_1") (pintype "passive"))
      (node (ref "LED7") (pin "1") (pinfunction "A_1") (pintype "passive"))
      (node (ref "LED8") (pin "1") (pinfunction "A_1") (pintype "passive"))
      (node (ref "RL1") (pin "3") (pinfunction "3_3") (pintype "passive"))
      (node (ref "RL2") (pin "3") (pinfunction "3_3") (pintype "passive"))
      (node (ref "RL3") (pin "3") (pinfunction "3_3") (pintype "passive"))
      (node (ref "RL4") (pin "3") (pinfunction "3_3") (pintype "passive"))
      (node (ref "RL5") (pin "3") (pinfunction "3_3") (pintype "passive"))
      (node (ref "RL6") (pin "3") (pinfunction "3_3") (pintype "passive"))
      (node (ref "RL7") (pin "3") (pinfunction "3_3") (pintype "passive"))
      (node (ref "U1") (pin "4") (pinfunction "C_4") (pintype "passive"))
      (node (ref "U2") (pin "4") (pinfunction "C_4") (pintype "passive"))
      (node (ref "U3") (pin "4") (pinfunction "C_4") (pintype "passive"))
      (node (ref "U4") (pin "4") (pinfunction "C_4") (pintype "passive"))
      (node (ref "U5") (pin "4") (pinfunction "C_4") (pintype "passive"))
      (node (ref "U6") (pin "4") (pinfunction "C_4") (pintype "passive"))
      (node (ref "U8") (pin "4") (pinfunction "C_4") (pintype "passive"))
    )
    (net (code "80") (name "VCC5_ISO") (class "Default")
      (node (ref "B1") (pin "4") (pinfunction "+VO_4") (pintype "passive"))
      (node (ref "C11") (pin "4") (pinfunction "4_4") (pintype "passive"))
      (node (ref "C12") (pin "3") (pinfunction "3_3") (pintype "passive"))
      (node (ref "C4") (pin "1") (pinfunction "1_1") (pintype "passive"))
      (node (ref "LED1") (pin "1") (pinfunction "A_1") (pintype "passive"))
      (node (ref "LED10") (pin "1") (pinfunction "A_1") (pintype "passive"))
      (node (ref "LED13") (pin "1") (pinfunction "A_1") (pintype "passive"))
      (node (ref "LED2") (pin "1") (pinfunction "A_1") (pintype "passive"))
      (node (ref "LED5") (pin "1") (pinfunction "A_1") (pintype "passive"))
      (node (ref "LED6") (pin "1") (pinfunction "A_1") (pintype "passive"))
      (node (ref "LED9") (pin "1") (pinfunction "A_1") (pintype "passive"))
      (node (ref "R1") (pin "2") (pinfunction "2_2") (pintype "passive"))
      (node (ref "R13") (pin "2") (pinfunction "2_2") (pintype "passive"))
      (node (ref "R14") (pin "2") (pinfunction "2_2") (pintype "passive"))
      (node (ref "R2") (pin "2") (pinfunction "2_2") (pintype "passive"))
      (node (ref "R25") (pin "2") (pinfunction "2_2") (pintype "passive"))
      (node (ref "R26") (pin "2") (pinfunction "2_2") (pintype "passive"))
      (node (ref "R37") (pin "2") (pinfunction "2_2") (pintype "passive"))
      (node (ref "U7") (pin "15") (pinfunction "VIN_15") (pintype "passive"))
    )
    (net (code "81") (name "VCC33_ISO") (class "Default")
      (node (ref "C8") (pin "3") (pinfunction "3_3") (pintype "passive"))
      (node (ref "U7") (pin "16") (pinfunction "3V3_16") (pintype "passive"))
    )
    (net (code "82") (name "VCC_IN") (class "Default")
      (node (ref "BUCK LM1") (pin "1") (pinfunction "IN+_1") (pintype "passive"))
      (node (ref "C1") (pin "2") (pinfunction "2_2") (pintype "passive"))
    )
    (net (code "84") (name "unconnected-(RL1-Pad2)") (class "Default")
      (node (ref "RL1") (pin "2") (pinfunction "2_2") (pintype "passive+no_connect"))
    )
    (net (code "85") (name "unconnected-(RL2-Pad2)") (class "Default")
      (node (ref "RL2") (pin "2") (pinfunction "2_2") (pintype "passive+no_connect"))
    )
    (net (code "86") (name "unconnected-(RL3-Pad2)") (class "Default")
      (node (ref "RL3") (pin "2") (pinfunction "2_2") (pintype "passive+no_connect"))
    )
    (net (code "87") (name "unconnected-(RL4-Pad2)") (class "Default")
      (node (ref "RL4") (pin "2") (pinfunction "2_2") (pintype "passive+no_connect"))
    )
    (net (code "88") (name "unconnected-(RL5-Pad2)") (class "Default")
      (node (ref "RL5") (pin "2") (pinfunction "2_2") (pintype "passive+no_connect"))
    )
    (net (code "89") (name "unconnected-(RL6-Pad2)") (class "Default")
      (node (ref "RL6") (pin "2") (pinfunction "2_2") (pintype "passive+no_connect"))
    )
    (net (code "90") (name "unconnected-(RL7-Pad2)") (class "Default")
      (node (ref "RL7") (pin "2") (pinfunction "2_2") (pintype "passive+no_connect"))
    )
    (net (code "91") (name "unconnected-(U7-D2-Pad19)") (class "Default")
      (node (ref "U7") (pin "19") (pinfunction "D2_19") (pintype "passive+no_connect"))
    )
    (net (code "92") (name "unconnected-(U7-D34-Pad4)") (class "Default")
      (node (ref "U7") (pin "4") (pinfunction "D34_4") (pintype "passive+no_connect"))
    )
    (net (code "93") (name "unconnected-(U7-D35-Pad5)") (class "Default")
      (node (ref "U7") (pin "5") (pinfunction "D35_5") (pintype "passive+no_connect"))
    )
    (net (code "94") (name "unconnected-(U7-EN-Pad1)") (class "Default")
      (node (ref "U7") (pin "1") (pinfunction "EN_1") (pintype "passive+no_connect"))
    )
    (net (code "95") (name "unconnected-(U7-GND-Pad17)") (class "Default")
      (node (ref "U7") (pin "17") (pinfunction "GND_17") (pintype "passive+no_connect"))
    )
    (net (code "96") (name "unconnected-(U7-RX0-Pad27)") (class "Default")
      (node (ref "U7") (pin "27") (pinfunction "RX0_27") (pintype "passive+no_connect"))
    )
    (net (code "97") (name "unconnected-(U7-TX0-Pad28)") (class "Default")
      (node (ref "U7") (pin "28") (pinfunction "TX0_28") (pintype "passive+no_connect"))
    )
    (net (code "98") (name "unconnected-(U7-VN-Pad3)") (class "Default")
      (node (ref "U7") (pin "3") (pinfunction "VN_3") (pintype "passive+no_connect"))
    )
  )
)
